# Rear_left_lamp_v2.net
KiCad netlist of a schematic drawn in EAGLE
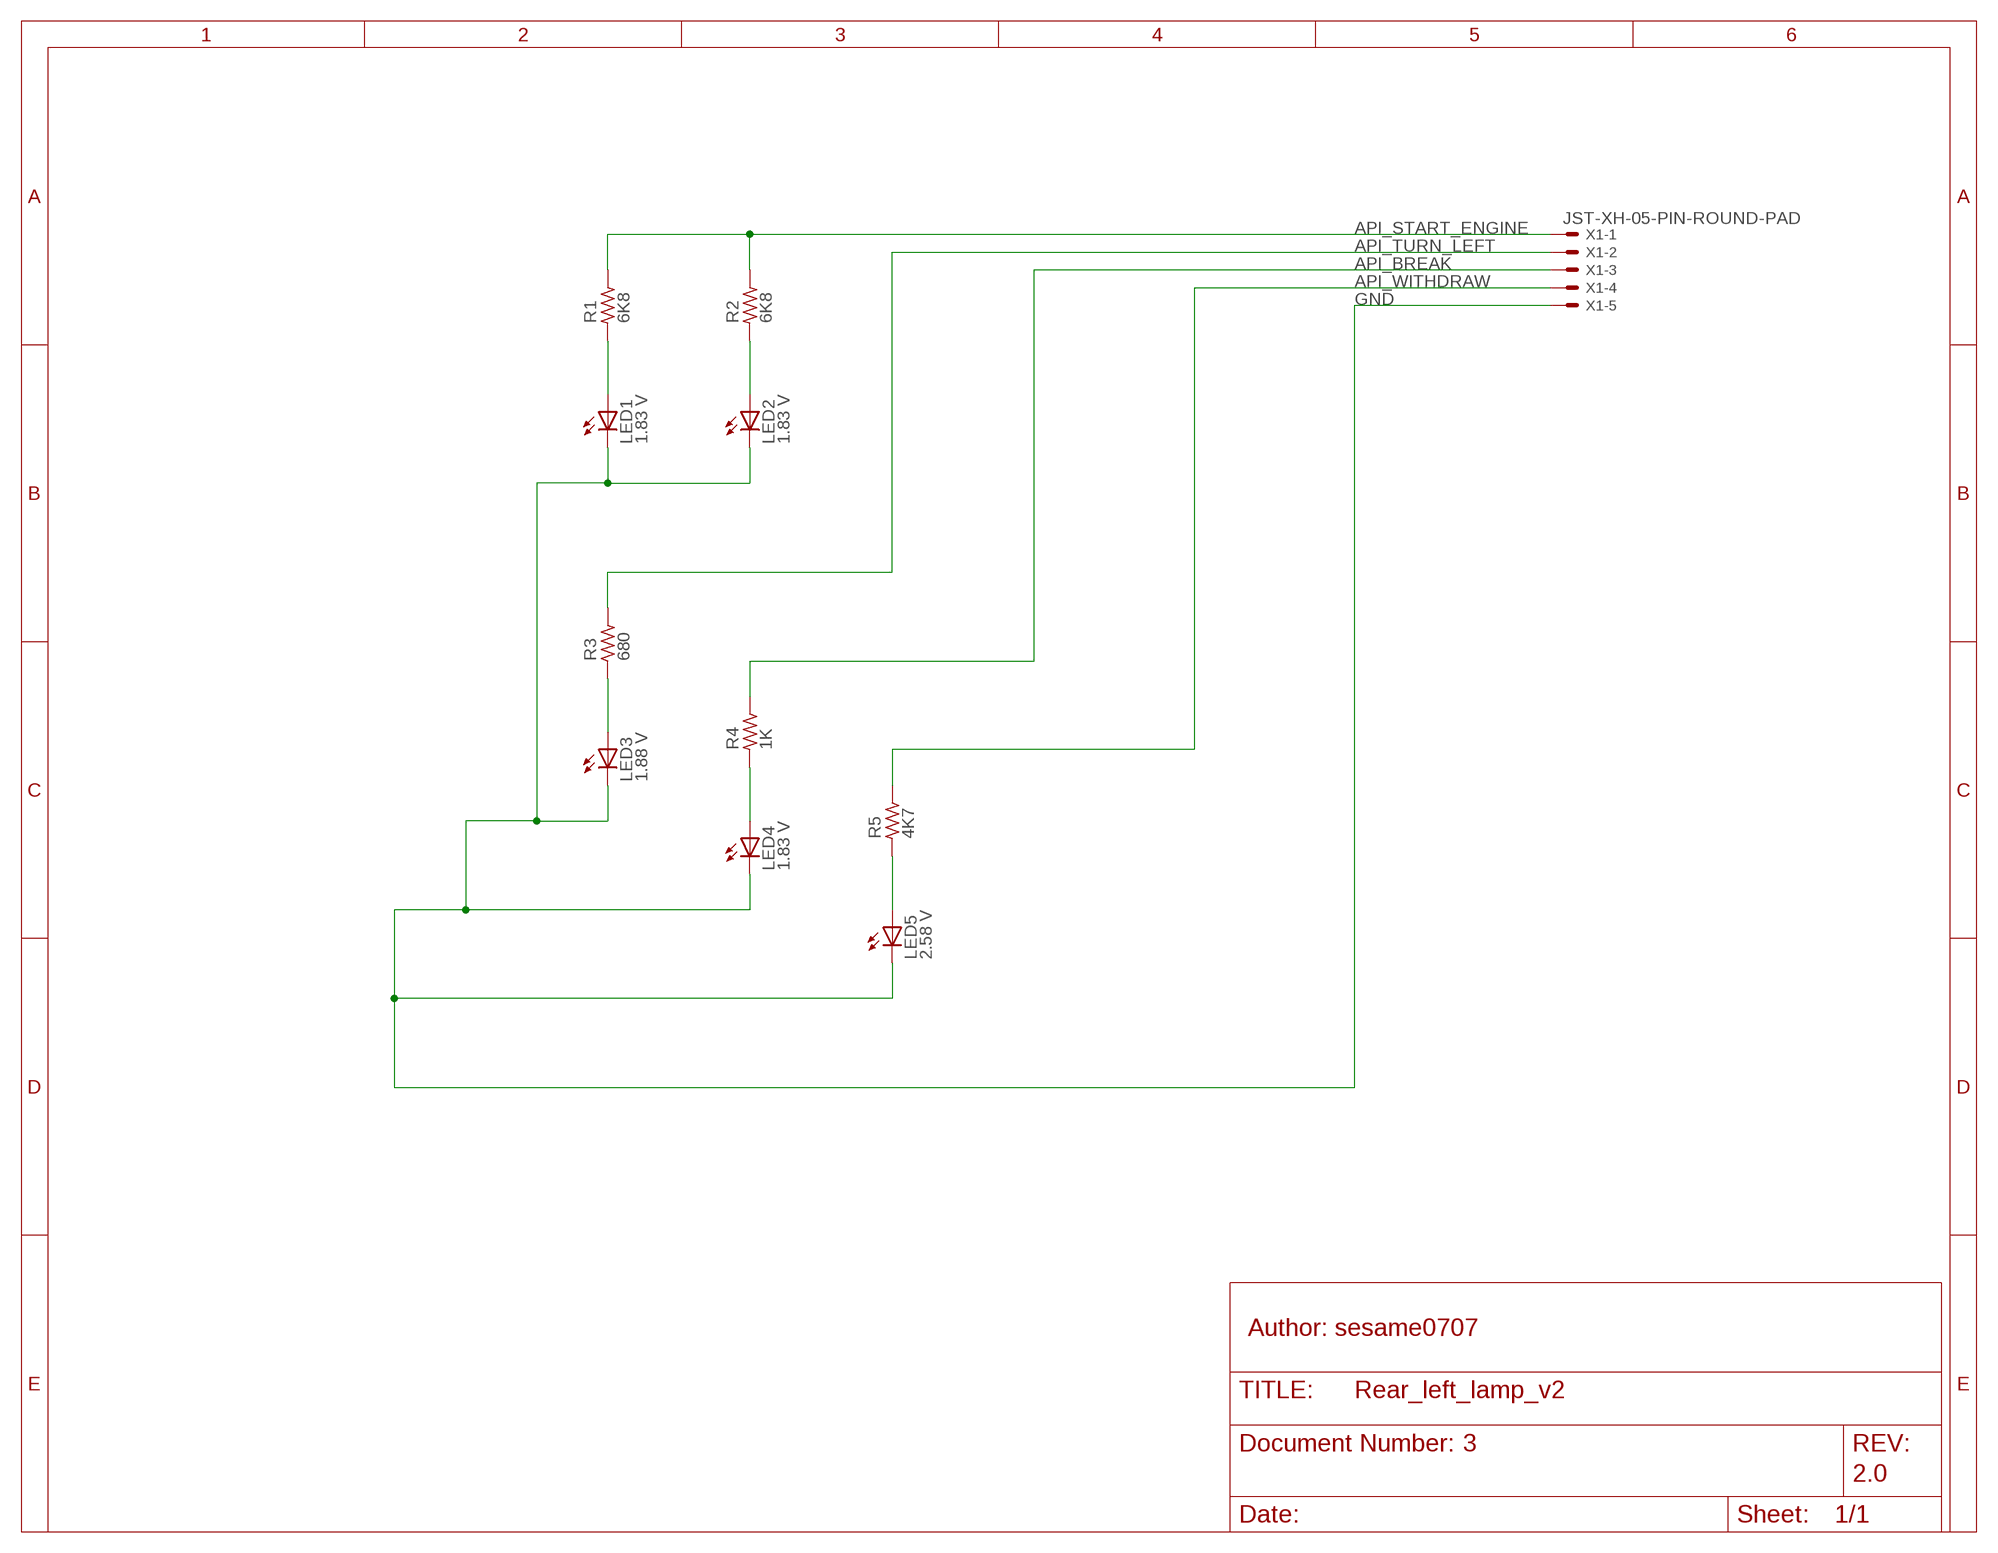
[diagram p0: schematic, sheet 1]

(export (version "E")
  (design (tool "Eeschema 10.0.6"))
  (components
    (comp (ref "LED1")
      (value "1.83 V")
      (footprint "eagle-import:LED5MM")
      (libsource (lib "eagle-import") (part "LED5MM"))
    )
    (comp (ref "LED2")
      (value "1.83 V")
      (footprint "eagle-import:LED5MM")
      (libsource (lib "eagle-import") (part "LED5MM"))
    )
    (comp (ref "LED3")
      (value "1.88 V")
      (footprint "eagle-import:LED5MM")
      (libsource (lib "eagle-import") (part "LED5MM"))
    )
    (comp (ref "LED4")
      (value "1.83 V")
      (footprint "eagle-import:LED5MM")
      (libsource (lib "eagle-import") (part "LED5MM"))
    )
    (comp (ref "LED5")
      (value "2.58 V")
      (footprint "eagle-import:LED5MM")
      (libsource (lib "eagle-import") (part "LED5MM"))
    )
    (comp (ref "R1")
      (value "6K8")
      (footprint "eagle-import:R0805")
      (libsource (lib "eagle-import") (part "R_0805"))
    )
    (comp (ref "R2")
      (value "6K8")
      (footprint "eagle-import:R0805")
      (libsource (lib "eagle-import") (part "R_0805"))
    )
    (comp (ref "R3")
      (value "680")
      (footprint "eagle-import:R0805")
      (libsource (lib "eagle-import") (part "R_0805"))
    )
    (comp (ref "R4")
      (value "1K")
      (footprint "eagle-import:R0805")
      (libsource (lib "eagle-import") (part "R_0805"))
    )
    (comp (ref "R5")
      (value "4K7")
      (footprint "eagle-import:R0805")
      (libsource (lib "eagle-import") (part "R_0805"))
    )
    (comp (ref "X1")
      (value "JST-XH-05-PIN-ROUND-PAD")
      (footprint "eagle-import:JST-XH-05-PACKAGE-ROUND-PAD")
      (libsource (lib "eagle-import") (part "JST-XH-05-PIN-ROUND-PAD"))
    )
  )
  (nets
    (net (code "1") (name "/API_BREAK") (class "Default")
      (node (ref "R4") (pin "2") (pinfunction "2_2") (pintype "passive"))
      (node (ref "X1") (pin "3") (pinfunction "S_3") (pintype "passive"))
    )
    (net (code "2") (name "/API_START_ENGINE") (class "Default")
      (node (ref "R1") (pin "2") (pinfunction "2_2") (pintype "passive"))
      (node (ref "R2") (pin "2") (pinfunction "2_2") (pintype "passive"))
      (node (ref "X1") (pin "1") (pinfunction "S_1") (pintype "passive"))
    )
    (net (code "3") (name "/API_TURN_LEFT") (class "Default")
      (node (ref "R3") (pin "2") (pinfunction "2_2") (pintype "passive"))
      (node (ref "X1") (pin "2") (pinfunction "S_2") (pintype "passive"))
    )
    (net (code "4") (name "/API_WITHDRAW") (class "Default")
      (node (ref "R5") (pin "2") (pinfunction "2_2") (pintype "passive"))
      (node (ref "X1") (pin "4") (pinfunction "S_4") (pintype "passive"))
    )
    (net (code "5") (name "/GND") (class "Default")
      (node (ref "LED1") (pin "K") (pinfunction "C_K") (pintype "passive"))
      (node (ref "LED2") (pin "K") (pinfunction "C_K") (pintype "passive"))
      (node (ref "LED3") (pin "K") (pinfunction "C_K") (pintype "passive"))
      (node (ref "LED4") (pin "K") (pinfunction "C_K") (pintype "passive"))
      (node (ref "LED5") (pin "K") (pinfunction "C_K") (pintype "passive"))
      (node (ref "X1") (pin "5") (pinfunction "S_5") (pintype "passive"))
    )
    (net (code "6") (name "Net-(LED1-PadA)") (class "Default")
      (node (ref "LED1") (pin "A") (pinfunction "A_A") (pintype "passive"))
      (node (ref "R1") (pin "1") (pinfunction "1_1") (pintype "passive"))
    )
    (net (code "7") (name "Net-(LED2-PadA)") (class "Default")
      (node (ref "LED2") (pin "A") (pinfunction "A_A") (pintype "passive"))
      (node (ref "R2") (pin "1") (pinfunction "1_1") (pintype "passive"))
    )
    (net (code "8") (name "Net-(LED3-PadA)") (class "Default")
      (node (ref "LED3") (pin "A") (pinfunction "A_A") (pintype "passive"))
      (node (ref "R3") (pin "1") (pinfunction "1_1") (pintype "passive"))
    )
    (net (code "9") (name "Net-(LED4-PadA)") (class "Default")
      (node (ref "LED4") (pin "A") (pinfunction "A_A") (pintype "passive"))
      (node (ref "R4") (pin "1") (pinfunction "1_1") (pintype "passive"))
    )
    (net (code "10") (name "Net-(LED5-PadA)") (class "Default")
      (node (ref "LED5") (pin "A") (pinfunction "A_A") (pintype "passive"))
      (node (ref "R5") (pin "1") (pinfunction "1_1") (pintype "passive"))
    )
  )
)
